# Sheet1.net
KiCad netlist of a schematic drawn in Altium Designer
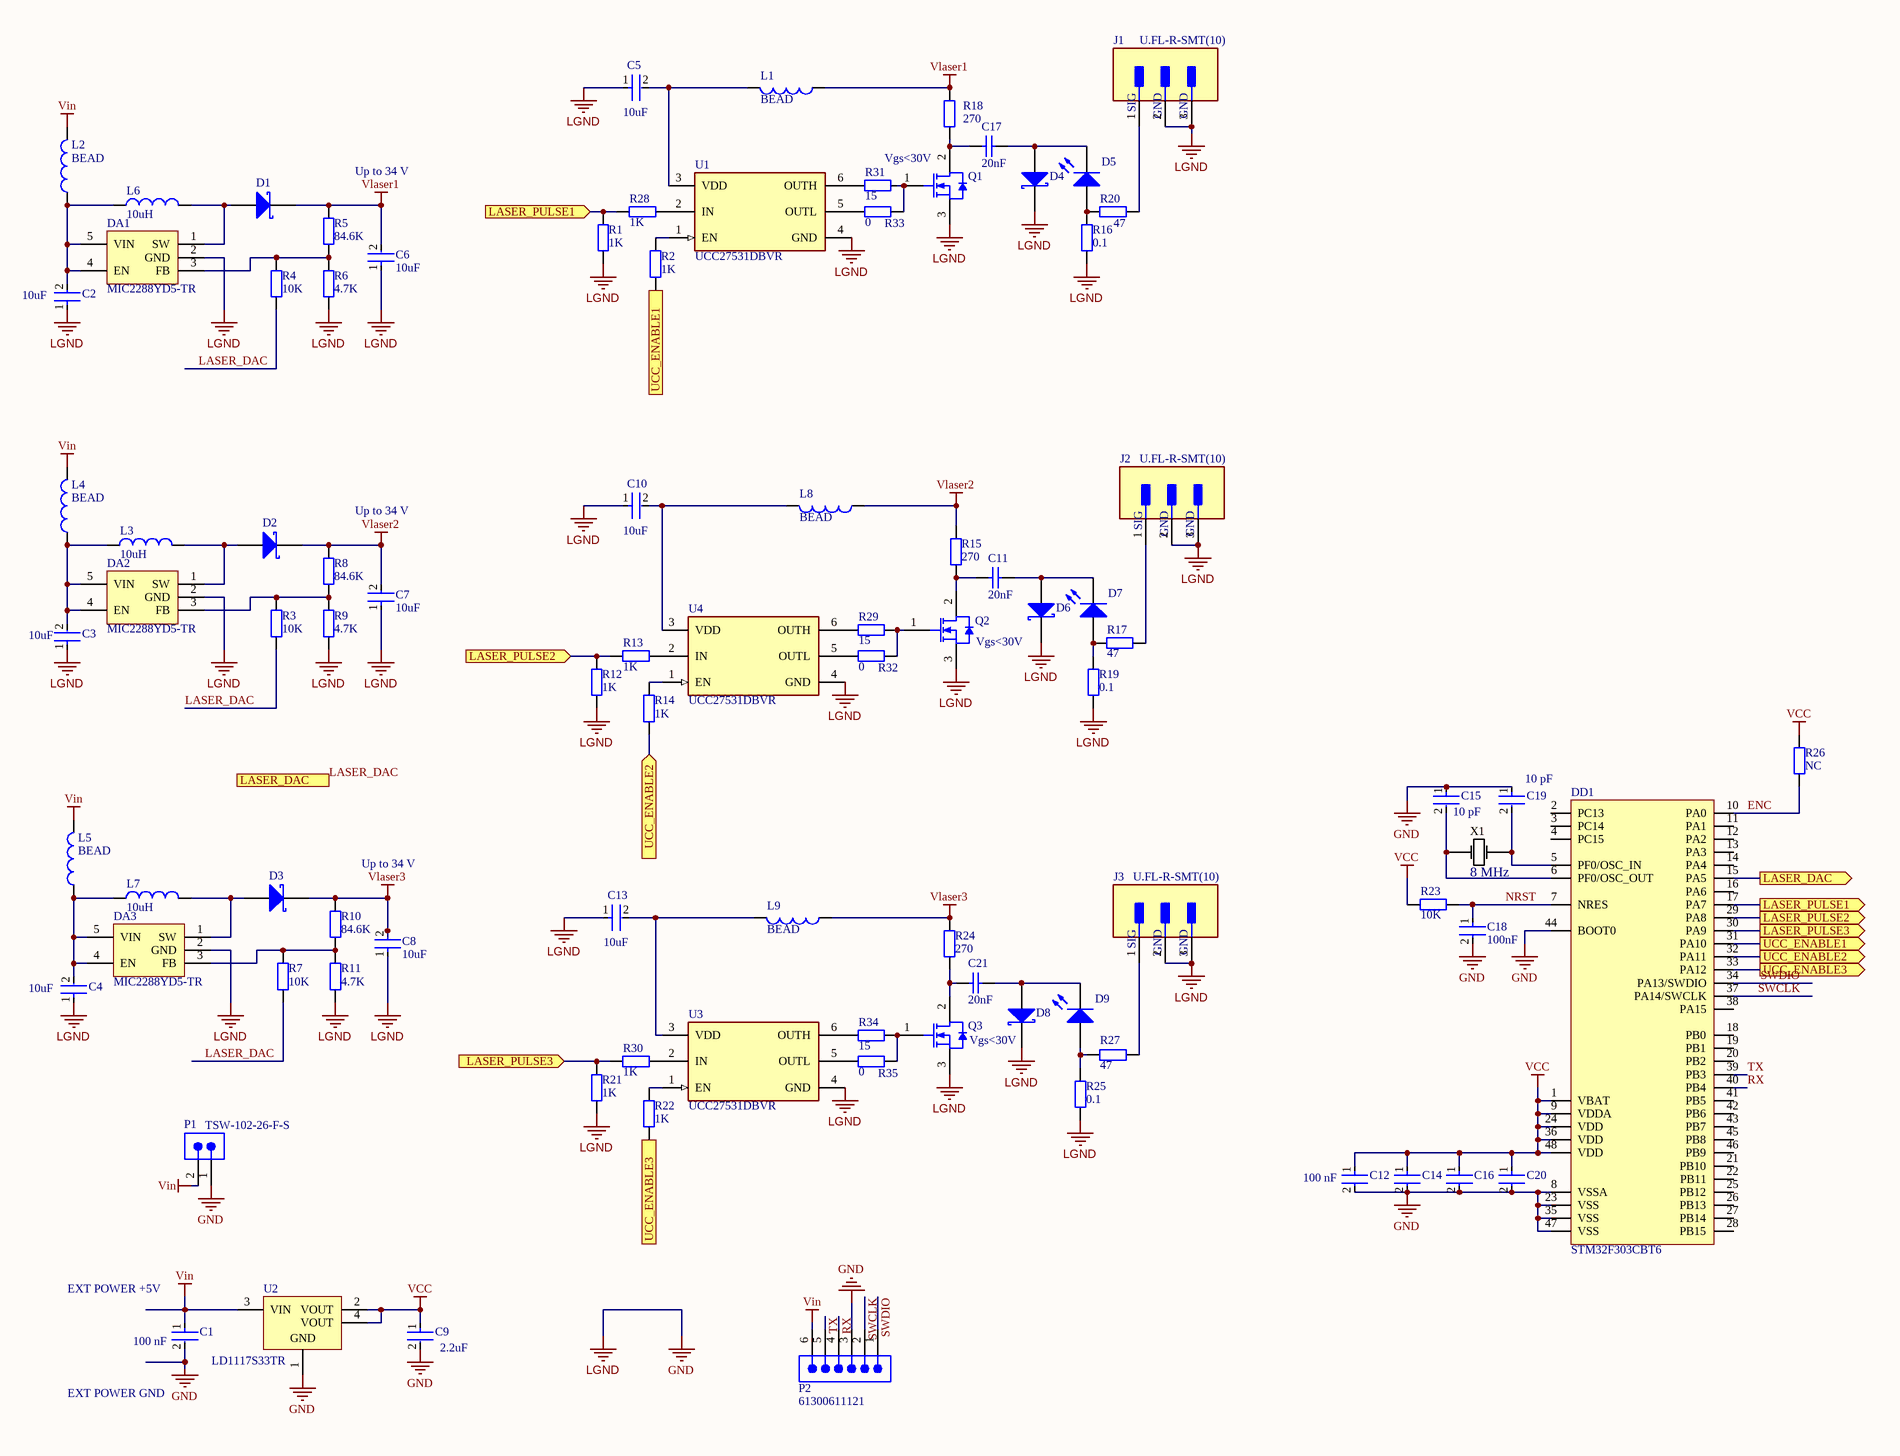
[diagram p0: Sheet1.SchDoc, right]

(export (version "E")
  (design (tool "Eeschema 10.0.6"))
  (components
    (comp (ref "C1")
      (value "100 nF")
      (footprint "FP-CC0603-DA-MFG")
      (description "CAP CER 0.1UF 16V X7R 0603")
      (fields
        (field (name "OCTOPART") "https://octopart.com/cc0603krx7r7bb104-yageo-192941")
        (field (name "TOLERANCE") "0.1")
      )
      (libsource (lib "Altium Content Vault") (part "11868f565c42a9108669ba33697ecf6"))
    )
    (comp (ref "C2")
      (value "10uF")
      (footprint "FP-CL31B106KBHNNNE-MFG")
      (description "CAP CER 10UF 50V X7R 1206")
      (fields (field (name "MANUFACTURER") "Samsung") (field (name "TOLERANCE") "10%"))
      (libsource (lib "Altium Content Vault") (part "b4654b650e69147ec39a6b967a45e02"))
    )
    (comp (ref "C3")
      (value "10uF")
      (footprint "FP-CL31B106KBHNNNE-MFG")
      (description "CAP CER 10UF 50V X7R 1206")
      (fields (field (name "MANUFACTURER") "Samsung") (field (name "TOLERANCE") "10%"))
      (libsource (lib "Altium Content Vault") (part "b4654b650e69147ec39a6b967a45e02"))
    )
    (comp (ref "C4")
      (value "10uF")
      (footprint "FP-CL31B106KBHNNNE-MFG")
      (description "CAP CER 10UF 50V X7R 1206")
      (fields (field (name "MANUFACTURER") "Samsung") (field (name "TOLERANCE") "10%"))
      (libsource (lib "Altium Content Vault") (part "b4654b650e69147ec39a6b967a45e02"))
    )
    (comp (ref "C5")
      (value "10uF")
      (footprint "FP-CL31B106KBHNNNE-MFG")
      (description "CAP CER 10UF 50V X7R 1206")
      (fields (field (name "MANUFACTURER") "Samsung") (field (name "TOLERANCE") "10%"))
      (libsource (lib "Altium Content Vault") (part "b4654b650e69147ec39a6b967a45e02"))
    )
    (comp (ref "C6")
      (value "10uF")
      (footprint "FP-CL31B106KBHNNNE-MFG")
      (description "CAP CER 10UF 50V X7R 1206")
      (fields (field (name "MANUFACTURER") "Samsung") (field (name "TOLERANCE") "10%"))
      (libsource (lib "Altium Content Vault") (part "b4654b650e69147ec39a6b967a45e02"))
    )
    (comp (ref "C7")
      (value "10uF")
      (footprint "FP-CL31B106KBHNNNE-MFG")
      (description "CAP CER 10UF 50V X7R 1206")
      (fields (field (name "MANUFACTURER") "Samsung") (field (name "TOLERANCE") "10%"))
      (libsource (lib "Altium Content Vault") (part "b4654b650e69147ec39a6b967a45e02"))
    )
    (comp (ref "C8")
      (value "10uF")
      (footprint "FP-CL31B106KBHNNNE-MFG")
      (description "CAP CER 10UF 50V X7R 1206")
      (fields (field (name "MANUFACTURER") "Samsung") (field (name "TOLERANCE") "10%"))
      (libsource (lib "Altium Content Vault") (part "b4654b650e69147ec39a6b967a45e02"))
    )
    (comp (ref "C9")
      (value "~")
      (footprint "FP-CL10-IPC_A")
      (description "Cap Ceramic 2.2uF 10V X7R ±10% Pad SMD 0603 +125°C T/R")
      (fields (field (name "CAPACITANCE") "2.2uF") (field (name "TOLERANCE") "10%"))
      (libsource (lib "Altium Content Vault") (part "b4654b650e69147ec39a6b967a45e02"))
    )
    (comp (ref "C10")
      (value "10uF")
      (footprint "FP-CL31B106KBHNNNE-MFG")
      (description "CAP CER 10UF 50V X7R 1206")
      (fields (field (name "MANUFACTURER") "Samsung") (field (name "TOLERANCE") "10%"))
      (libsource (lib "Altium Content Vault") (part "b4654b650e69147ec39a6b967a45e02"))
    )
    (comp (ref "C11")
      (value "20nF")
      (footprint "RESC2013X60X35NL10T20")
      (description "Chip capacitor")
      (fields (field (name "VOLTAGE") "50V"))
      (libsource (lib "MyLibSch") (part "CC0805"))
    )
    (comp (ref "C12")
      (value "CC0805KRX7R9BB104")
      (footprint "FP-CC0805-0_85-MFG")
      (description "CAP CER 0.1UF 50V X7R 0805")
      (fields
        (field (name "TOLERANCE") "0.1")
        (field (name "CAPACITANCE") "100 nF")
        (field (name "MANUFACTURER") "Yageo")
      )
      (libsource (lib "Altium Content Vault") (part "11868f565c42a9108669ba33697ecf6"))
    )
    (comp (ref "C13")
      (value "10uF")
      (footprint "FP-CL31B106KBHNNNE-MFG")
      (description "CAP CER 10UF 50V X7R 1206")
      (fields (field (name "MANUFACTURER") "Samsung") (field (name "TOLERANCE") "10%"))
      (libsource (lib "Altium Content Vault") (part "b4654b650e69147ec39a6b967a45e02"))
    )
    (comp (ref "C14")
      (value "CC0805KRX7R9BB104")
      (footprint "FP-CC0805-0_85-MFG")
      (description "CAP CER 0.1UF 50V X7R 0805")
      (fields (field (name "TOLERANCE") "0.1") (field (name "MANUFACTURER") "Yageo"))
      (libsource (lib "Altium Content Vault") (part "11868f565c42a9108669ba33697ecf6"))
    )
    (comp (ref "C15")
      (value "10 pF")
      (footprint "FP-C0805C-DN-MFG")
      (description "C0805 10 pF X7R 30ppm/°C 5.00% 50 V")
      (fields
        (field (name "OCTOPART") "https://octopart.com/c0805c100j5ractu-kemet-81794931")
        (field (name "MANUFACTURER PART NUMBER") "C0805C100J5RACTU")
      )
      (libsource (lib "Altium Content Vault") (part "b4654b650e69147ec39a6b967a45e02"))
    )
    (comp (ref "C16")
      (value "CC0805KRX7R9BB104")
      (footprint "FP-CC0805-0_85-MFG")
      (description "CAP CER 0.1UF 50V X7R 0805")
      (fields (field (name "TOLERANCE") "0.1") (field (name "MANUFACTURER") "Yageo"))
      (libsource (lib "Altium Content Vault") (part "11868f565c42a9108669ba33697ecf6"))
    )
    (comp (ref "C17")
      (value "20nF")
      (footprint "RESC2013X60X35ML10T20")
      (description "Chip capacitor")
      (fields (field (name "VOLTAGE") "50V"))
      (libsource (lib "MyLibSch") (part "CC0805"))
    )
    (comp (ref "C18")
      (value "100nF")
      (footprint "FP-CC0805-0_85-MFG")
      (description "CAP CER 0.1UF 50V X7R 0805")
      (fields (field (name "TOLERANCE") "0.1") (field (name "MANUFACTURER PART NUMBER") "CC0805KRX7R9BB104"))
      (libsource (lib "Altium Content Vault") (part "11868f565c42a9108669ba33697ecf6"))
    )
    (comp (ref "C19")
      (value "10 pF")
      (footprint "FP-C0805C-DN-MFG")
      (description "C0805 10 pF X7R 30ppm/°C 5.00% 50 V")
      (fields
        (field (name "OCTOPART") "https://octopart.com/c0805c100j5ractu-kemet-81794931")
        (field (name "MANUFACTURER PART NUMBER") "C0805C100J5RACTU")
      )
      (libsource (lib "Altium Content Vault") (part "b4654b650e69147ec39a6b967a45e02"))
    )
    (comp (ref "C20")
      (value "CC0805KRX7R9BB104")
      (footprint "FP-CC0805-0_85-MFG")
      (description "CAP CER 0.1UF 50V X7R 0805")
      (fields (field (name "TOLERANCE") "0.1") (field (name "MANUFACTURER") "Yageo"))
      (libsource (lib "Altium Content Vault") (part "11868f565c42a9108669ba33697ecf6"))
    )
    (comp (ref "C21")
      (value "20nF")
      (footprint "RESC2013X60X35NL10T20")
      (description "Chip capacitor")
      (fields (field (name "VOLTAGE") "50V"))
      (libsource (lib "MyLibSch") (part "CC0805"))
    )
    (comp (ref "D1")
      (value "Schottky Diode")
      (footprint "FP-PG-SC79-2-MFG")
      (libsource (lib "Simulation Generic Components") (part "Schottky Diode"))
    )
    (comp (ref "D2")
      (value "Schottky Diode")
      (footprint "FP-PG-SC79-2-MFG")
      (libsource (lib "Simulation Generic Components") (part "Schottky Diode"))
    )
    (comp (ref "D3")
      (value "Schottky Diode")
      (footprint "FP-PG-SC79-2-MFG")
      (libsource (lib "Simulation Generic Components") (part "Schottky Diode"))
    )
    (comp (ref "D4")
      (value "Schottky Diode")
      (footprint "FP-PG-SC79-2-MFG")
      (libsource (lib "Simulation Generic Components") (part "Schottky Diode"))
    )
    (comp (ref "D5")
      (value "Light-Emitting Diode")
      (footprint "FP-DPGEW1S09H-MFG")
      (libsource (lib "Simulation Generic Components") (part "LED"))
    )
    (comp (ref "D6")
      (value "Schottky Diode")
      (footprint "FP-PG-SC79-2-MFG")
      (libsource (lib "Simulation Generic Components") (part "Schottky Diode"))
    )
    (comp (ref "D7")
      (value "Light-Emitting Diode")
      (footprint "FP-DPGEW1S09H-MFG")
      (libsource (lib "Simulation Generic Components") (part "LED"))
    )
    (comp (ref "D8")
      (value "Schottky Diode")
      (footprint "FP-PG-SC79-2-MFG")
      (libsource (lib "Simulation Generic Components") (part "Schottky Diode"))
    )
    (comp (ref "D9")
      (value "Light-Emitting Diode")
      (footprint "FP-DPGEW1S09H-MFG")
      (libsource (lib "Simulation Generic Components") (part "LED"))
    )
    (comp (ref "DA1")
      (value "MIC2288YD5-TR")
      (footprint "TSOT-23-5:FP-TSOT-5LD-PL-1-IPC_A")
      (description "Step Up")
      (libsource (lib "lcd_lib") (part "MIC2288"))
    )
    (comp (ref "DA2")
      (value "MIC2288YD5-TR")
      (footprint "FP-TSOT-5LD-PL-1-IPC_A")
      (description "Step Up")
      (libsource (lib "lcd_lib") (part "MIC2288"))
    )
    (comp (ref "DA3")
      (value "MIC2288YD5-TR")
      (footprint "FP-TSOT-5LD-PL-1-IPC_A")
      (description "Step Up")
      (libsource (lib "lcd_lib") (part "MIC2288"))
    )
    (comp (ref "DD1")
      (value "STM32F303CBT6")
      (footprint "STM-LQFP48_L")
      (description "Microcontroller")
      (libsource (lib "lcd_lib") (part "STM32F3_LQFP48"))
    )
    (comp (ref "J1")
      (value "U.FL-R-SMT(10)")
      (footprint "FP-U_FL-R-SMT_10-MFG")
      (description "CONN U.FL RCPT STR 50 OHM SMD")
      (libsource (lib "Altium Content Vault") (part "eef6fde44c591823e8076210edfe12f"))
    )
    (comp (ref "J2")
      (value "U.FL-R-SMT(10)")
      (footprint "FP-U_FL-R-SMT_10-MFG")
      (description "CONN U.FL RCPT STR 50 OHM SMD")
      (libsource (lib "Altium Content Vault") (part "eef6fde44c591823e8076210edfe12f"))
    )
    (comp (ref "J3")
      (value "U.FL-R-SMT(10)")
      (footprint "FP-U_FL-R-SMT_10-MFG")
      (description "CONN U.FL RCPT STR 50 OHM SMD")
      (libsource (lib "Altium Content Vault") (part "eef6fde44c591823e8076210edfe12f"))
    )
    (comp (ref "L1")
      (value "BEAD")
      (footprint "FP-BLM18-0_15-t0_8-IPC_A")
      (description "Ferrit Bead")
      (libsource (lib "MyLibSch") (part "BEAD"))
    )
    (comp (ref "L2")
      (value "BEAD")
      (footprint "FP-BLM18-0_15-t0_8-IPC_A")
      (description "Ferrit Bead")
      (libsource (lib "MyLibSch") (part "BEAD"))
    )
    (comp (ref "L3")
      (value "10uH")
      (footprint "RESC2013X60X35LL10T20")
      (description "Inductor")
      (libsource (lib "Simulation Generic Components") (part "Inductor"))
    )
    (comp (ref "L4")
      (value "BEAD")
      (footprint "FP-BLM18-0_15-t0_8-IPC_A")
      (description "Ferrit Bead")
      (libsource (lib "MyLibSch") (part "BEAD"))
    )
    (comp (ref "L5")
      (value "BEAD")
      (footprint "FP-BLM18-0_15-t0_8-IPC_A")
      (description "Ferrit Bead")
      (libsource (lib "MyLibSch") (part "BEAD"))
    )
    (comp (ref "L6")
      (value "10uH")
      (footprint "RESC2013X60X35LL10T20")
      (description "Inductor")
      (libsource (lib "Simulation Generic Components") (part "Inductor"))
    )
    (comp (ref "L7")
      (value "10uH")
      (footprint "RESC2013X60X35LL10T20")
      (description "Inductor")
      (libsource (lib "Simulation Generic Components") (part "Inductor"))
    )
    (comp (ref "L8")
      (value "BEAD")
      (footprint "FP-BLM18-0_15-t0_8-IPC_A")
      (description "Ferrit Bead")
      (libsource (lib "MyLibSch") (part "BEAD"))
    )
    (comp (ref "L9")
      (value "BEAD")
      (footprint "FP-BLM18-0_15-t0_8-IPC_A")
      (description "Ferrit Bead")
      (libsource (lib "MyLibSch") (part "BEAD"))
    )
    (comp (ref "P1")
      (value "TSW-102-26-F-S")
      (footprint "SMTC-TSW-102-26-XX-S")
      (description "0.025\" SQ Post Header, Through-hole, Vertical, -55 to 125 degC, 2.54 mm Pitch, 2-Pin, Male, RoHS")
      (fields (field (name "MANUFACTURER") "Samtec"))
      (libsource (lib "Altium Content Vault") (part "SMTC-TSW-102-X-X-S-X"))
    )
    (comp (ref "P2")
      (value "61300611121")
      (footprint "61300611121")
      (libsource (lib "Altium Content Vault") (part "Header_Male_1R_06P"))
    )
    (comp (ref "Q1")
      (value "~")
      (footprint "INF-PG-TO252-3-313_N")
      (fields (field (name "MANUFACTURER") "Infineon") (field (name "PARTNUMBER") "IPD60R520C6"))
      (libsource (lib "Components - 15.04.25 - 21.51") (part "CMP-1164-00353-1"))
    )
    (comp (ref "Q2")
      (value "~")
      (footprint "INF-PG-TO252-3-313_N")
      (fields (field (name "MANUFACTURER") "Infineon") (field (name "PARTNUMBER") "IPD60R520C6"))
      (libsource (lib "Components - 15.04.25 - 21.51") (part "CMP-1164-00353-1"))
    )
    (comp (ref "Q3")
      (value "~")
      (footprint "INF-PG-TO252-3-313_N")
      (fields (field (name "MANUFACTURER") "Infineon") (field (name "PARTNUMBER") "IPD60R520C6"))
      (libsource (lib "Components - 15.04.25 - 21.51") (part "CMP-1164-00353-1"))
    )
    (comp (ref "R1")
      (value "1K")
      (footprint "RESC2013X60X35ML10T20")
      (description "Chip resistor")
      (fields (field (name "TOLERANCE") "5%"))
      (libsource (lib "") (part "RC0805_1"))
    )
    (comp (ref "R2")
      (value "1K")
      (footprint "RESC2013X60X35ML10T20")
      (description "Chip resistor")
      (fields (field (name "TOLERANCE") "5%"))
      (libsource (lib "") (part "RC0805_1"))
    )
    (comp (ref "R3")
      (value "10K")
      (footprint "RESC2013X60X35ML10T20")
      (description "Chip resistor")
      (fields (field (name "TOLERANCE") "5%"))
      (libsource (lib "") (part "RC0805_1"))
    )
    (comp (ref "R4")
      (value "10K")
      (footprint "RESC2013X60X35ML10T20")
      (description "Chip resistor")
      (fields (field (name "TOLERANCE") "5%"))
      (libsource (lib "") (part "RC0805_1"))
    )
    (comp (ref "R5")
      (value "84.6K")
      (footprint "RESC2013X60X35ML10T20")
      (description "Chip resistor")
      (fields (field (name "TOLERANCE") "5%"))
      (libsource (lib "") (part "RC0805_1"))
    )
    (comp (ref "R6")
      (value "4.7K")
      (footprint "RESC2013X60X35ML10T20")
      (description "Chip resistor")
      (fields (field (name "TOLERANCE") "5%"))
      (libsource (lib "") (part "RC0805_1"))
    )
    (comp (ref "R7")
      (value "10K")
      (footprint "RESC2013X60X35ML10T20")
      (description "Chip resistor")
      (fields (field (name "TOLERANCE") "5%"))
      (libsource (lib "") (part "RC0805_1"))
    )
    (comp (ref "R8")
      (value "84.6K")
      (footprint "RESC2013X60X35ML10T20")
      (description "Chip resistor")
      (fields (field (name "TOLERANCE") "5%"))
      (libsource (lib "") (part "RC0805_1"))
    )
    (comp (ref "R9")
      (value "4.7K")
      (footprint "RESC2013X60X35ML10T20")
      (description "Chip resistor")
      (fields (field (name "TOLERANCE") "5%"))
      (libsource (lib "") (part "RC0805_1"))
    )
    (comp (ref "R10")
      (value "84.6K")
      (footprint "RESC2013X60X35ML10T20")
      (description "Chip resistor")
      (fields (field (name "TOLERANCE") "5%"))
      (libsource (lib "") (part "RC0805_1"))
    )
    (comp (ref "R11")
      (value "4.7K")
      (footprint "RESC2013X60X35ML10T20")
      (description "Chip resistor")
      (fields (field (name "TOLERANCE") "5%"))
      (libsource (lib "") (part "RC0805_1"))
    )
    (comp (ref "R12")
      (value "1K")
      (footprint "RESC2013X60X35ML10T20")
      (description "Chip resistor")
      (fields (field (name "TOLERANCE") "5%"))
      (libsource (lib "") (part "RC0805_1"))
    )
    (comp (ref "R13")
      (value "1K")
      (footprint "RESC2013X60X35ML10T20")
      (description "Chip resistor")
      (fields (field (name "TOLERANCE") "5%"))
      (libsource (lib "") (part "RC0805_2"))
    )
    (comp (ref "R14")
      (value "1K")
      (footprint "RESC2013X60X35ML10T20")
      (description "Chip resistor")
      (fields (field (name "TOLERANCE") "5%"))
      (libsource (lib "") (part "RC0805_1"))
    )
    (comp (ref "R15")
      (value "270")
      (footprint "FP-CL31B106KBHNNNE-IPC_A")
      (description "Chip resistor")
      (fields (field (name "TOLERANCE") "5%"))
      (libsource (lib "") (part "RC0805_1"))
    )
    (comp (ref "R16")
      (value "0.1")
      (footprint "FP-LLL215-0_1-IPC_B")
      (description "Chip resistor")
      (fields (field (name "TOLERANCE") "5%"))
      (libsource (lib "") (part "RC0805_1"))
    )
    (comp (ref "R17")
      (value "47")
      (footprint "RESC2013X60X35ML10T20")
      (description "Chip resistor")
      (fields (field (name "TOLERANCE") "5%"))
      (libsource (lib "") (part "RC0805_2"))
    )
    (comp (ref "R18")
      (value "270")
      (footprint "FP-CL31B106KBHNNNE-IPC_A")
      (description "Chip resistor")
      (fields (field (name "TOLERANCE") "5%"))
      (libsource (lib "") (part "RC0805_1"))
    )
    (comp (ref "R19")
      (value "0.1")
      (footprint "FP-LLL215-0_1-IPC_B")
      (description "Chip resistor")
      (fields (field (name "TOLERANCE") "5%"))
      (libsource (lib "") (part "RC0805_1"))
    )
    (comp (ref "R20")
      (value "47")
      (footprint "RESC2013X60X35ML10T20")
      (description "Chip resistor")
      (fields (field (name "TOLERANCE") "5%"))
      (libsource (lib "MyLibSch") (part "RC0805"))
    )
    (comp (ref "R21")
      (value "1K")
      (footprint "RESC2013X60X35ML10T20")
      (description "Chip resistor")
      (fields (field (name "TOLERANCE") "5%"))
      (libsource (lib "") (part "RC0805_1"))
    )
    (comp (ref "R22")
      (value "1K")
      (footprint "RESC2013X60X35ML10T20")
      (description "Chip resistor")
      (fields (field (name "TOLERANCE") "5%"))
      (libsource (lib "") (part "RC0805_1"))
    )
    (comp (ref "R23")
      (value "10K")
      (footprint "RESC2013X60X35ML10T20")
      (description "Chip resistor")
      (fields (field (name "TOLERANCE") "5%"))
      (libsource (lib "MyLibSch") (part "RC0805"))
    )
    (comp (ref "R24")
      (value "270")
      (footprint "FP-CL31B106KBHNNNE-IPC_A")
      (description "Chip resistor")
      (fields (field (name "TOLERANCE") "5%"))
      (libsource (lib "") (part "RC0805_1"))
    )
    (comp (ref "R25")
      (value "0.1")
      (footprint "FP-LLL215-0_1-IPC_B")
      (description "Chip resistor")
      (fields (field (name "TOLERANCE") "5%"))
      (libsource (lib "") (part "RC0805_1"))
    )
    (comp (ref "R26")
      (value "NC")
      (footprint "RESC2013X60X35ML10T20")
      (description "Chip resistor")
      (fields (field (name "TOLERANCE") "5%"))
      (libsource (lib "") (part "RC0805_3"))
    )
    (comp (ref "R27")
      (value "47")
      (footprint "RESC2013X60X35ML10T20")
      (description "Chip resistor")
      (fields (field (name "TOLERANCE") "5%"))
      (libsource (lib "MyLibSch") (part "RC0805"))
    )
    (comp (ref "R28")
      (value "1K")
      (footprint "RESC2013X60X35ML10T20")
      (description "Chip resistor")
      (fields (field (name "TOLERANCE") "5%"))
      (libsource (lib "") (part "RC0805_2"))
    )
    (comp (ref "R29")
      (value "15")
      (footprint "RESC2013X60X35ML10T20")
      (description "Chip resistor")
      (fields (field (name "TOLERANCE") "5%"))
      (libsource (lib "") (part "RC0805_2"))
    )
    (comp (ref "R30")
      (value "1K")
      (footprint "RESC2013X60X35ML10T20")
      (description "Chip resistor")
      (fields (field (name "TOLERANCE") "5%"))
      (libsource (lib "") (part "RC0805_2"))
    )
    (comp (ref "R31")
      (value "15")
      (footprint "RESC2013X60X35ML10T20")
      (description "Chip resistor")
      (fields (field (name "TOLERANCE") "5%"))
      (libsource (lib "") (part "RC0805_2"))
    )
    (comp (ref "R32")
      (value "0")
      (footprint "RESC2013X60X35ML10T20")
      (description "Chip resistor")
      (fields (field (name "TOLERANCE") "5%"))
      (libsource (lib "") (part "RC0805_2"))
    )
    (comp (ref "R33")
      (value "0")
      (footprint "RESC2013X60X35ML10T20")
      (description "Chip resistor")
      (fields (field (name "TOLERANCE") "5%"))
      (libsource (lib "") (part "RC0805_2"))
    )
    (comp (ref "R34")
      (value "15")
      (footprint "RESC2013X60X35ML10T20")
      (description "Chip resistor")
      (fields (field (name "TOLERANCE") "5%"))
      (libsource (lib "") (part "RC0805_2"))
    )
    (comp (ref "R35")
      (value "0")
      (footprint "RESC2013X60X35ML10T20")
      (description "Chip resistor")
      (fields (field (name "TOLERANCE") "5%"))
      (libsource (lib "") (part "RC0805_2"))
    )
    (comp (ref "U1")
      (value "UCC27531DBVR")
      (footprint "FP-DBV0006A-IPC_B")
      (description "IC GATE DRVR LOW-SIDE SOT23-6")
      (libsource (lib "Altium Content Vault") (part "16a91a241c20d76ff8c7580b319091c"))
    )
    (comp (ref "U2")
      (value "LD1117S33TR")
      (footprint "SOT-223_L")
      (description "Fixed Low Drop Positive Voltage Regulator, 3.3V, 4-Pin SOT-223, Tape and Reel")
      (libsource (lib "Altium Content Vault") (part "PM-REG-LD1117-SOT4"))
    )
    (comp (ref "U3")
      (value "UCC27531DBVR")
      (footprint "FP-DBV0006A-IPC_B")
      (description "IC GATE DRVR LOW-SIDE SOT23-6")
      (libsource (lib "Altium Content Vault") (part "16a91a241c20d76ff8c7580b319091c"))
    )
    (comp (ref "U4")
      (value "UCC27531DBVR")
      (footprint "FP-DBV0006A-IPC_B")
      (description "IC GATE DRVR LOW-SIDE SOT23-6")
      (libsource (lib "Altium Content Vault") (part "16a91a241c20d76ff8c7580b319091c"))
    )
    (comp (ref "X1")
      (value "8 MHz")
      (footprint "FP-ASFL1-MFG")
      (description "Quartz_SX-6 (SMD06035C4)")
      (fields (field (name "Comment") "Quartz"))
      (libsource (lib "lcd_lib") (part "Quartz_SX-6"))
    )
  )
  (nets
    (net (code "1") (name "/ENC") (class "Default")
      (node (ref "DD1") (pin "10") (pinfunction "PA0_10") (pintype "passive"))
      (node (ref "R26") (pin "2") (pinfunction "2_2") (pintype "passive"))
    )
    (net (code "2") (name "/LASER_DAC") (class "Default")
      (node (ref "DD1") (pin "15") (pinfunction "PA5_15") (pintype "passive"))
      (node (ref "R3") (pin "1") (pinfunction "1_1") (pintype "passive"))
      (node (ref "R4") (pin "1") (pinfunction "1_1") (pintype "passive"))
      (node (ref "R7") (pin "1") (pinfunction "1_1") (pintype "passive"))
    )
    (net (code "3") (name "/LASER_PULSE1") (class "Default")
      (node (ref "DD1") (pin "17") (pinfunction "PA7_17") (pintype "passive"))
      (node (ref "R1") (pin "2") (pinfunction "2_2") (pintype "passive"))
      (node (ref "R28") (pin "2") (pinfunction "2_2") (pintype "passive"))
    )
    (net (code "4") (name "/LASER_PULSE2") (class "Default")
      (node (ref "DD1") (pin "29") (pinfunction "PA8_29") (pintype "passive"))
      (node (ref "R12") (pin "2") (pinfunction "2_2") (pintype "passive"))
      (node (ref "R13") (pin "2") (pinfunction "2_2") (pintype "passive"))
    )
    (net (code "5") (name "/LASER_PULSE3") (class "Default")
      (node (ref "DD1") (pin "30") (pinfunction "PA9_30") (pintype "passive"))
      (node (ref "R21") (pin "2") (pinfunction "2_2") (pintype "passive"))
      (node (ref "R30") (pin "2") (pinfunction "2_2") (pintype "passive"))
    )
    (net (code "6") (name "/NRST") (class "Default")
      (node (ref "C18") (pin "1") (pinfunction "1_1") (pintype "passive"))
      (node (ref "DD1") (pin "7") (pinfunction "NRES_7") (pintype "passive"))
      (node (ref "R23") (pin "2") (pinfunction "2_2") (pintype "passive"))
    )
    (net (code "7") (name "/RX") (class "Default")
      (node (ref "DD1") (pin "40") (pinfunction "PB4_40") (pintype "passive"))
      (node (ref "P2") (pin "4") (pinfunction "4_4") (pintype "passive"))
    )
    (net (code "8") (name "/SWCLK") (class "Default")
      (node (ref "DD1") (pin "37") (pinfunction "PA14/SWCLK_37") (pintype "passive"))
      (node (ref "P2") (pin "2") (pinfunction "2_2") (pintype "passive"))
    )
    (net (code "9") (name "/SWDIO") (class "Default")
      (node (ref "DD1") (pin "34") (pinfunction "PA13/SWDIO_34") (pintype "passive"))
      (node (ref "P2") (pin "1") (pinfunction "1_1") (pintype "passive"))
    )
    (net (code "10") (name "/TX") (class "Default")
      (node (ref "DD1") (pin "39") (pinfunction "PB3_39") (pintype "passive"))
      (node (ref "P2") (pin "5") (pinfunction "5_5") (pintype "passive"))
    )
    (net (code "11") (name "/UCC_ENABLE1") (class "Default")
      (node (ref "DD1") (pin "31") (pinfunction "PA10_31") (pintype "passive"))
      (node (ref "R2") (pin "1") (pinfunction "1_1") (pintype "passive"))
    )
    (net (code "12") (name "/UCC_ENABLE2") (class "Default")
      (node (ref "DD1") (pin "32") (pinfunction "PA11_32") (pintype "passive"))
      (node (ref "R14") (pin "1") (pinfunction "1_1") (pintype "passive"))
    )
    (net (code "13") (name "/UCC_ENABLE3") (class "Default")
      (node (ref "DD1") (pin "33") (pinfunction "PA12_33") (pintype "passive"))
      (node (ref "R22") (pin "1") (pinfunction "1_1") (pintype "passive"))
    )
    (net (code "14") (name "GND") (class "Default")
      (node (ref "C1") (pin "2") (pinfunction "2_2") (pintype "passive"))
      (node (ref "C10") (pin "1") (pinfunction "1_1") (pintype "passive"))
      (node (ref "C12") (pin "2") (pinfunction "2_2") (pintype "passive"))
      (node (ref "C13") (pin "1") (pinfunction "1_1") (pintype "passive"))
      (node (ref "C14") (pin "2") (pinfunction "2_2") (pintype "passive"))
      (node (ref "C15") (pin "1") (pinfunction "1_1") (pintype "passive"))
      (node (ref "C16") (pin "2") (pinfunction "2_2") (pintype "passive"))
      (node (ref "C18") (pin "2") (pinfunction "2_2") (pintype "passive"))
      (node (ref "C19") (pin "1") (pinfunction "1_1") (pintype "passive"))
      (node (ref "C2") (pin "1") (pinfunction "1_1") (pintype "passive"))
      (node (ref "C20") (pin "2") (pinfunction "2_2") (pintype "passive"))
      (node (ref "C3") (pin "1") (pinfunction "1_1") (pintype "passive"))
      (node (ref "C4") (pin "1") (pinfunction "1_1") (pintype "passive"))
      (node (ref "C5") (pin "1") (pinfunction "1_1") (pintype "passive"))
      (node (ref "C6") (pin "1") (pinfunction "1_1") (pintype "passive"))
      (node (ref "C7") (pin "1") (pinfunction "1_1") (pintype "passive"))
      (node (ref "C8") (pin "1") (pinfunction "1_1") (pintype "passive"))
      (node (ref "C9") (pin "2") (pinfunction "2_2") (pintype "passive"))
      (node (ref "D4") (pin "2") (pinfunction "K_2") (pintype "passive"))
      (node (ref "D6") (pin "2") (pinfunction "K_2") (pintype "passive"))
      (node (ref "D8") (pin "2") (pinfunction "K_2") (pintype "passive"))
      (node (ref "DA1") (pin "2") (pinfunction "GND_2") (pintype "power_in"))
      (node (ref "DA2") (pin "2") (pinfunction "GND_2") (pintype "power_in"))
      (node (ref "DA3") (pin "2") (pinfunction "GND_2") (pintype "power_in"))
      (node (ref "DD1") (pin "23") (pinfunction "VSS_23") (pintype "passive"))
      (node (ref "DD1") (pin "35") (pinfunction "VSS_35") (pintype "passive"))
      (node (ref "DD1") (pin "44") (pinfunction "BOOT0_44") (pintype "passive"))
      (node (ref "DD1") (pin "47") (pinfunction "VSS_47") (pintype "passive"))
      (node (ref "DD1") (pin "8") (pinfunction "VSSA_8") (pintype "passive"))
      (node (ref "J1") (pin "2") (pinfunction "GND_2") (pintype "power_in"))
      (node (ref "J1") (pin "3") (pinfunction "GND_3") (pintype "power_in"))
      (node (ref "J2") (pin "2") (pinfunction "GND_2") (pintype "power_in"))
      (node (ref "J2") (pin "3") (pinfunction "GND_3") (pintype "power_in"))
      (node (ref "J3") (pin "2") (pinfunction "GND_2") (pintype "power_in"))
      (node (ref "J3") (pin "3") (pinfunction "GND_3") (pintype "power_in"))
      (node (ref "P1") (pin "1") (pinfunction "1_1") (pintype "passive"))
      (node (ref "P2") (pin "3") (pinfunction "3_3") (pintype "passive"))
      (node (ref "Q1") (pin "3") (pinfunction "SOURCE_3") (pintype "passive"))
      (node (ref "Q2") (pin "3") (pinfunction "SOURCE_3") (pintype "passive"))
      (node (ref "Q3") (pin "3") (pinfunction "SOURCE_3") (pintype "passive"))
      (node (ref "R1") (pin "1") (pinfunction "1_1") (pintype "passive"))
      (node (ref "R11") (pin "1") (pinfunction "1_1") (pintype "passive"))
      (node (ref "R12") (pin "1") (pinfunction "1_1") (pintype "passive"))
      (node (ref "R16") (pin "1") (pinfunction "1_1") (pintype "passive"))
      (node (ref "R19") (pin "1") (pinfunction "1_1") (pintype "passive"))
      (node (ref "R21") (pin "1") (pinfunction "1_1") (pintype "passive"))
      (node (ref "R25") (pin "1") (pinfunction "1_1") (pintype "passive"))
      (node (ref "R6") (pin "1") (pinfunction "1_1") (pintype "passive"))
      (node (ref "R9") (pin "1") (pinfunction "1_1") (pintype "passive"))
      (node (ref "U1") (pin "4") (pinfunction "GND_4") (pintype "power_in"))
      (node (ref "U2") (pin "1") (pinfunction "GND_1") (pintype "power_in"))
      (node (ref "U3") (pin "4") (pinfunction "GND_4") (pintype "power_in"))
      (node (ref "U4") (pin "4") (pinfunction "GND_4") (pintype "power_in"))
    )
    (net (code "15") (name "Net-(D1-A)") (class "Default")
      (node (ref "D1") (pin "1") (pinfunction "A_1") (pintype "passive"))
      (node (ref "DA1") (pin "1") (pinfunction "SW_1") (pintype "open_collector"))
      (node (ref "L6") (pin "2") (pinfunction "2_2") (pintype "passive"))
    )
    (net (code "16") (name "Net-(D2-A)") (class "Default")
      (node (ref "D2") (pin "1") (pinfunction "A_1") (pintype "passive"))
      (node (ref "DA2") (pin "1") (pinfunction "SW_1") (pintype "open_collector"))
      (node (ref "L3") (pin "2") (pinfunction "2_2") (pintype "passive"))
    )
    (net (code "17") (name "Net-(D3-A)") (class "Default")
      (node (ref "D3") (pin "1") (pinfunction "A_1") (pintype "passive"))
      (node (ref "DA3") (pin "1") (pinfunction "SW_1") (pintype "open_collector"))
      (node (ref "L7") (pin "2") (pinfunction "2_2") (pintype "passive"))
    )
    (net (code "18") (name "Net-(D4-A)") (class "Default")
      (node (ref "C17") (pin "1") (pinfunction "1_1") (pintype "passive"))
      (node (ref "D4") (pin "1") (pinfunction "A_1") (pintype "passive"))
      (node (ref "D5") (pin "2") (pinfunction "K_2") (pintype "passive"))
    )
    (net (code "19") (name "Net-(D5-A)") (class "Default")
      (node (ref "D5") (pin "1") (pinfunction "A_1") (pintype "passive"))
      (node (ref "R16") (pin "2") (pinfunction "2_2") (pintype "passive"))
      (node (ref "R20") (pin "1") (pinfunction "1_1") (pintype "passive"))
    )
    (net (code "20") (name "Net-(D6-A)") (class "Default")
      (node (ref "C11") (pin "1") (pinfunction "1_1") (pintype "passive"))
      (node (ref "D6") (pin "1") (pinfunction "A_1") (pintype "passive"))
      (node (ref "D7") (pin "2") (pinfunction "K_2") (pintype "passive"))
    )
    (net (code "21") (name "Net-(D7-A)") (class "Default")
      (node (ref "D7") (pin "1") (pinfunction "A_1") (pintype "passive"))
      (node (ref "R17") (pin "2") (pinfunction "2_2") (pintype "passive"))
      (node (ref "R19") (pin "2") (pinfunction "2_2") (pintype "passive"))
    )
    (net (code "22") (name "Net-(D8-A)") (class "Default")
      (node (ref "C21") (pin "1") (pinfunction "1_1") (pintype "passive"))
      (node (ref "D8") (pin "1") (pinfunction "A_1") (pintype "passive"))
      (node (ref "D9") (pin "2") (pinfunction "K_2") (pintype "passive"))
    )
    (net (code "23") (name "Net-(D9-A)") (class "Default")
      (node (ref "D9") (pin "1") (pinfunction "A_1") (pintype "passive"))
      (node (ref "R25") (pin "2") (pinfunction "2_2") (pintype "passive"))
      (node (ref "R27") (pin "1") (pinfunction "1_1") (pintype "passive"))
    )
    (net (code "24") (name "Net-(DA1-EN)") (class "Default")
      (node (ref "C2") (pin "2") (pinfunction "2_2") (pintype "passive"))
      (node (ref "DA1") (pin "4") (pinfunction "EN_4") (pintype "power_in"))
      (node (ref "DA1") (pin "5") (pinfunction "VIN_5") (pintype "passive"))
      (node (ref "L2") (pin "1") (pinfunction "1_1") (pintype "passive"))
      (node (ref "L6") (pin "1") (pinfunction "1_1") (pintype "passive"))
    )
    (net (code "25") (name "Net-(DA1-FB)") (class "Default")
      (node (ref "DA1") (pin "3") (pinfunction "FB_3") (pintype "power_in"))
      (node (ref "R4") (pin "2") (pinfunction "2_2") (pintype "passive"))
      (node (ref "R5") (pin "1") (pinfunction "1_1") (pintype "passive"))
      (node (ref "R6") (pin "2") (pinfunction "2_2") (pintype "passive"))
    )
    (net (code "26") (name "Net-(DA2-EN)") (class "Default")
      (node (ref "C3") (pin "2") (pinfunction "2_2") (pintype "passive"))
      (node (ref "DA2") (pin "4") (pinfunction "EN_4") (pintype "power_in"))
      (node (ref "DA2") (pin "5") (pinfunction "VIN_5") (pintype "passive"))
      (node (ref "L3") (pin "1") (pinfunction "1_1") (pintype "passive"))
      (node (ref "L4") (pin "1") (pinfunction "1_1") (pintype "passive"))
    )
    (net (code "27") (name "Net-(DA2-FB)") (class "Default")
      (node (ref "DA2") (pin "3") (pinfunction "FB_3") (pintype "power_in"))
      (node (ref "R3") (pin "2") (pinfunction "2_2") (pintype "passive"))
      (node (ref "R8") (pin "1") (pinfunction "1_1") (pintype "passive"))
      (node (ref "R9") (pin "2") (pinfunction "2_2") (pintype "passive"))
    )
    (net (code "28") (name "Net-(DA3-EN)") (class "Default")
      (node (ref "C4") (pin "2") (pinfunction "2_2") (pintype "passive"))
      (node (ref "DA3") (pin "4") (pinfunction "EN_4") (pintype "power_in"))
      (node (ref "DA3") (pin "5") (pinfunction "VIN_5") (pintype "passive"))
      (node (ref "L5") (pin "1") (pinfunction "1_1") (pintype "passive"))
      (node (ref "L7") (pin "1") (pinfunction "1_1") (pintype "passive"))
    )
    (net (code "29") (name "Net-(DA3-FB)") (class "Default")
      (node (ref "DA3") (pin "3") (pinfunction "FB_3") (pintype "power_in"))
      (node (ref "R10") (pin "1") (pinfunction "1_1") (pintype "passive"))
      (node (ref "R11") (pin "2") (pinfunction "2_2") (pintype "passive"))
      (node (ref "R7") (pin "2") (pinfunction "2_2") (pintype "passive"))
    )
    (net (code "30") (name "Net-(DD1-PF0{slash}OSC_IN)") (class "Default")
      (node (ref "C19") (pin "2") (pinfunction "2_2") (pintype "passive"))
      (node (ref "DD1") (pin "5") (pinfunction "PF0/OSC_IN_5") (pintype "passive"))
      (node (ref "X1") (pin "3") (pinfunction "3_3") (pintype "passive"))
    )
    (net (code "31") (name "Net-(DD1-PF0{slash}OSC_OUT)") (class "Default")
      (node (ref "C15") (pin "2") (pinfunction "2_2") (pintype "passive"))
      (node (ref "DD1") (pin "6") (pinfunction "PF0/OSC_OUT_6") (pintype "passive"))
      (node (ref "X1") (pin "1") (pinfunction "1_1") (pintype "passive"))
    )
    (net (code "32") (name "Net-(J1-SIG)") (class "Default")
      (node (ref "J1") (pin "1") (pinfunction "SIG_1") (pintype "passive"))
      (node (ref "R20") (pin "2") (pinfunction "2_2") (pintype "passive"))
    )
    (net (code "33") (name "Net-(J2-SIG)") (class "Default")
      (node (ref "J2") (pin "1") (pinfunction "SIG_1") (pintype "passive"))
      (node (ref "R17") (pin "1") (pinfunction "1_1") (pintype "passive"))
    )
    (net (code "34") (name "Net-(J3-SIG)") (class "Default")
      (node (ref "J3") (pin "1") (pinfunction "SIG_1") (pintype "passive"))
      (node (ref "R27") (pin "2") (pinfunction "2_2") (pintype "passive"))
    )
    (net (code "35") (name "Net-(Q1-DRAIN)") (class "Default")
      (node (ref "C17") (pin "2") (pinfunction "2_2") (pintype "passive"))
      (node (ref "Q1") (pin "2") (pinfunction "DRAIN_2") (pintype "passive"))
      (node (ref "R18") (pin "1") (pinfunction "1_1") (pintype "passive"))
    )
    (net (code "36") (name "Net-(Q1-GATE)") (class "Default")
      (node (ref "Q1") (pin "1") (pinfunction "GATE_1") (pintype "passive"))
      (node (ref "R31") (pin "1") (pinfunction "1_1") (pintype "passive"))
      (node (ref "R33") (pin "1") (pinfunction "1_1") (pintype "passive"))
    )
    (net (code "37") (name "Net-(Q2-DRAIN)") (class "Default")
      (node (ref "C11") (pin "2") (pinfunction "2_2") (pintype "passive"))
      (node (ref "Q2") (pin "2") (pinfunction "DRAIN_2") (pintype "passive"))
      (node (ref "R15") (pin "1") (pinfunction "1_1") (pintype "passive"))
    )
    (net (code "38") (name "Net-(Q2-GATE)") (class "Default")
      (node (ref "Q2") (pin "1") (pinfunction "GATE_1") (pintype "passive"))
      (node (ref "R29") (pin "1") (pinfunction "1_1") (pintype "passive"))
      (node (ref "R32") (pin "1") (pinfunction "1_1") (pintype "passive"))
    )
    (net (code "39") (name "Net-(Q3-DRAIN)") (class "Default")
      (node (ref "C21") (pin "2") (pinfunction "2_2") (pintype "passive"))
      (node (ref "Q3") (pin "2") (pinfunction "DRAIN_2") (pintype "passive"))
      (node (ref "R24") (pin "1") (pinfunction "1_1") (pintype "passive"))
    )
    (net (code "40") (name "Net-(Q3-GATE)") (class "Default")
      (node (ref "Q3") (pin "1") (pinfunction "GATE_1") (pintype "passive"))
      (node (ref "R34") (pin "1") (pinfunction "1_1") (pintype "passive"))
      (node (ref "R35") (pin "1") (pinfunction "1_1") (pintype "passive"))
    )
    (net (code "41") (name "Net-(U1-EN)") (class "Default")
      (node (ref "R2") (pin "2") (pinfunction "2_2") (pintype "passive"))
      (node (ref "U1") (pin "1") (pinfunction "EN_1") (pintype "input"))
    )
    (net (code "42") (name "Net-(U1-IN)") (class "Default")
      (node (ref "R28") (pin "1") (pinfunction "1_1") (pintype "passive"))
      (node (ref "U1") (pin "2") (pinfunction "IN_2") (pintype "tri_state"))
    )
    (net (code "43") (name "Net-(U1-OUTH)") (class "Default")
      (node (ref "R31") (pin "2") (pinfunction "2_2") (pintype "passive"))
      (node (ref "U1") (pin "6") (pinfunction "OUTH_6") (pintype "passive"))
    )
    (net (code "44") (name "Net-(U1-OUTL)") (class "Default")
      (node (ref "R33") (pin "2") (pinfunction "2_2") (pintype "passive"))
      (node (ref "U1") (pin "5") (pinfunction "OUTL_5") (pintype "passive"))
    )
    (net (code "45") (name "Net-(U1-VDD)") (class "Default")
      (node (ref "C5") (pin "2") (pinfunction "2_2") (pintype "passive"))
      (node (ref "L1") (pin "2") (pinfunction "2_2") (pintype "passive"))
      (node (ref "U1") (pin "3") (pinfunction "VDD_3") (pintype "power_in"))
    )
    (net (code "46") (name "Net-(U3-EN)") (class "Default")
      (node (ref "R22") (pin "2") (pinfunction "2_2") (pintype "passive"))
      (node (ref "U3") (pin "1") (pinfunction "EN_1") (pintype "input"))
    )
    (net (code "47") (name "Net-(U3-IN)") (class "Default")
      (node (ref "R30") (pin "1") (pinfunction "1_1") (pintype "passive"))
      (node (ref "U3") (pin "2") (pinfunction "IN_2") (pintype "tri_state"))
    )
    (net (code "48") (name "Net-(U3-OUTH)") (class "Default")
      (node (ref "R34") (pin "2") (pinfunction "2_2") (pintype "passive"))
      (node (ref "U3") (pin "6") (pinfunction "OUTH_6") (pintype "passive"))
    )
    (net (code "49") (name "Net-(U3-OUTL)") (class "Default")
      (node (ref "R35") (pin "2") (pinfunction "2_2") (pintype "passive"))
      (node (ref "U3") (pin "5") (pinfunction "OUTL_5") (pintype "passive"))
    )
    (net (code "50") (name "Net-(U3-VDD)") (class "Default")
      (node (ref "C13") (pin "2") (pinfunction "2_2") (pintype "passive"))
      (node (ref "L9") (pin "2") (pinfunction "2_2") (pintype "passive"))
      (node (ref "U3") (pin "3") (pinfunction "VDD_3") (pintype "power_in"))
    )
    (net (code "51") (name "Net-(U4-EN)") (class "Default")
      (node (ref "R14") (pin "2") (pinfunction "2_2") (pintype "passive"))
      (node (ref "U4") (pin "1") (pinfunction "EN_1") (pintype "input"))
    )
    (net (code "52") (name "Net-(U4-IN)") (class "Default")
      (node (ref "R13") (pin "1") (pinfunction "1_1") (pintype "passive"))
      (node (ref "U4") (pin "2") (pinfunction "IN_2") (pintype "tri_state"))
    )
    (net (code "53") (name "Net-(U4-OUTH)") (class "Default")
      (node (ref "R29") (pin "2") (pinfunction "2_2") (pintype "passive"))
      (node (ref "U4") (pin "6") (pinfunction "OUTH_6") (pintype "passive"))
    )
    (net (code "54") (name "Net-(U4-OUTL)") (class "Default")
      (node (ref "R32") (pin "2") (pinfunction "2_2") (pintype "passive"))
      (node (ref "U4") (pin "5") (pinfunction "OUTL_5") (pintype "passive"))
    )
    (net (code "55") (name "Net-(U4-VDD)") (class "Default")
      (node (ref "C10") (pin "2") (pinfunction "2_2") (pintype "passive"))
      (node (ref "L8") (pin "2") (pinfunction "2_2") (pintype "passive"))
      (node (ref "U4") (pin "3") (pinfunction "VDD_3") (pintype "power_in"))
    )
    (net (code "56") (name "VCC") (class "Default")
      (node (ref "C12") (pin "1") (pinfunction "1_1") (pintype "passive"))
      (node (ref "C14") (pin "1") (pinfunction "1_1") (pintype "passive"))
      (node (ref "C16") (pin "1") (pinfunction "1_1") (pintype "passive"))
      (node (ref "C20") (pin "1") (pinfunction "1_1") (pintype "passive"))
      (node (ref "C9") (pin "1") (pinfunction "1_1") (pintype "passive"))
      (node (ref "DD1") (pin "1") (pinfunction "VBAT_1") (pintype "passive"))
      (node (ref "DD1") (pin "24") (pinfunction "VDD_24") (pintype "passive"))
      (node (ref "DD1") (pin "36") (pinfunction "VDD_36") (pintype "passive"))
      (node (ref "DD1") (pin "48") (pinfunction "VDD_48") (pintype "passive"))
      (node (ref "DD1") (pin "9") (pinfunction "VDDA_9") (pintype "passive"))
      (node (ref "R23") (pin "1") (pinfunction "1_1") (pintype "passive"))
      (node (ref "R26") (pin "1") (pinfunction "1_1") (pintype "passive"))
      (node (ref "U2") (pin "2") (pinfunction "VOUT_2") (pintype "power_in"))
      (node (ref "U2") (pin "4") (pinfunction "VOUT_4") (pintype "power_in"))
    )
    (net (code "57") (name "Vin") (class "Default")
      (node (ref "C1") (pin "1") (pinfunction "1_1") (pintype "passive"))
      (node (ref "L2") (pin "2") (pinfunction "2_2") (pintype "passive"))
      (node (ref "L4") (pin "2") (pinfunction "2_2") (pintype "passive"))
      (node (ref "L5") (pin "2") (pinfunction "2_2") (pintype "passive"))
      (node (ref "P1") (pin "2") (pinfunction "2_2") (pintype "passive"))
      (node (ref "P2") (pin "6") (pinfunction "6_6") (pintype "passive"))
      (node (ref "U2") (pin "3") (pinfunction "VIN_3") (pintype "power_in"))
    )
    (net (code "58") (name "Vlaser1") (class "Default")
      (node (ref "C6") (pin "2") (pinfunction "2_2") (pintype "passive"))
      (node (ref "D1") (pin "2") (pinfunction "K_2") (pintype "passive"))
      (node (ref "L1") (pin "1") (pinfunction "1_1") (pintype "passive"))
      (node (ref "R18") (pin "2") (pinfunction "2_2") (pintype "passive"))
      (node (ref "R5") (pin "2") (pinfunction "2_2") (pintype "passive"))
    )
    (net (code "59") (name "Vlaser2") (class "Default")
      (node (ref "C7") (pin "2") (pinfunction "2_2") (pintype "passive"))
      (node (ref "D2") (pin "2") (pinfunction "K_2") (pintype "passive"))
      (node (ref "L8") (pin "1") (pinfunction "1_1") (pintype "passive"))
      (node (ref "R15") (pin "2") (pinfunction "2_2") (pintype "passive"))
      (node (ref "R8") (pin "2") (pinfunction "2_2") (pintype "passive"))
    )
    (net (code "60") (name "Vlaser3") (class "Default")
      (node (ref "C8") (pin "2") (pinfunction "2_2") (pintype "passive"))
      (node (ref "D3") (pin "2") (pinfunction "K_2") (pintype "passive"))
      (node (ref "L9") (pin "1") (pinfunction "1_1") (pintype "passive"))
      (node (ref "R10") (pin "2") (pinfunction "2_2") (pintype "passive"))
      (node (ref "R24") (pin "2") (pinfunction "2_2") (pintype "passive"))
    )
    (net (code "61") (name "unconnected-(DD1-PA1-Pad11)") (class "Default")
      (node (ref "DD1") (pin "11") (pinfunction "PA1_11") (pintype "passive"))
    )
    (net (code "62") (name "unconnected-(DD1-PA2-Pad12)") (class "Default")
      (node (ref "DD1") (pin "12") (pinfunction "PA2_12") (pintype "passive"))
    )
    (net (code "63") (name "unconnected-(DD1-PA3-Pad13)") (class "Default")
      (node (ref "DD1") (pin "13") (pinfunction "PA3_13") (pintype "passive"))
    )
    (net (code "64") (name "unconnected-(DD1-PA4-Pad14)") (class "Default")
      (node (ref "DD1") (pin "14") (pinfunction "PA4_14") (pintype "passive"))
    )
    (net (code "65") (name "unconnected-(DD1-PA6-Pad16)") (class "Default")
      (node (ref "DD1") (pin "16") (pinfunction "PA6_16") (pintype "passive"))
    )
    (net (code "66") (name "unconnected-(DD1-PA15-Pad38)") (class "Default")
      (node (ref "DD1") (pin "38") (pinfunction "PA15_38") (pintype "passive"))
    )
    (net (code "67") (name "unconnected-(DD1-PB0-Pad18)") (class "Default")
      (node (ref "DD1") (pin "18") (pinfunction "PB0_18") (pintype "passive"))
    )
    (net (code "68") (name "unconnected-(DD1-PB1-Pad19)") (class "Default")
      (node (ref "DD1") (pin "19") (pinfunction "PB1_19") (pintype "passive"))
    )
    (net (code "69") (name "unconnected-(DD1-PB2-Pad20)") (class "Default")
      (node (ref "DD1") (pin "20") (pinfunction "PB2_20") (pintype "passive"))
    )
    (net (code "70") (name "unconnected-(DD1-PB5-Pad41)") (class "Default")
      (node (ref "DD1") (pin "41") (pinfunction "PB5_41") (pintype "passive"))
    )
    (net (code "71") (name "unconnected-(DD1-PB6-Pad42)") (class "Default")
      (node (ref "DD1") (pin "42") (pinfunction "PB6_42") (pintype "passive"))
    )
    (net (code "72") (name "unconnected-(DD1-PB7-Pad43)") (class "Default")
      (node (ref "DD1") (pin "43") (pinfunction "PB7_43") (pintype "passive"))
    )
    (net (code "73") (name "unconnected-(DD1-PB8-Pad45)") (class "Default")
      (node (ref "DD1") (pin "45") (pinfunction "PB8_45") (pintype "passive"))
    )
    (net (code "74") (name "unconnected-(DD1-PB9-Pad46)") (class "Default")
      (node (ref "DD1") (pin "46") (pinfunction "PB9_46") (pintype "passive"))
    )
    (net (code "75") (name "unconnected-(DD1-PB10-Pad21)") (class "Default")
      (node (ref "DD1") (pin "21") (pinfunction "PB10_21") (pintype "passive"))
    )
    (net (code "76") (name "unconnected-(DD1-PB11-Pad22)") (class "Default")
      (node (ref "DD1") (pin "22") (pinfunction "PB11_22") (pintype "passive"))
    )
    (net (code "77") (name "unconnected-(DD1-PB12-Pad25)") (class "Default")
      (node (ref "DD1") (pin "25") (pinfunction "PB12_25") (pintype "passive"))
    )
    (net (code "78") (name "unconnected-(DD1-PB13-Pad26)") (class "Default")
      (node (ref "DD1") (pin "26") (pinfunction "PB13_26") (pintype "passive"))
    )
    (net (code "79") (name "unconnected-(DD1-PB14-Pad27)") (class "Default")
      (node (ref "DD1") (pin "27") (pinfunction "PB14_27") (pintype "passive"))
    )
    (net (code "80") (name "unconnected-(DD1-PB15-Pad28)") (class "Default")
      (node (ref "DD1") (pin "28") (pinfunction "PB15_28") (pintype "passive"))
    )
    (net (code "81") (name "unconnected-(DD1-PC13-Pad2)") (class "Default")
      (node (ref "DD1") (pin "2") (pinfunction "PC13_2") (pintype "passive"))
    )
    (net (code "82") (name "unconnected-(DD1-PC14-Pad3)") (class "Default")
      (node (ref "DD1") (pin "3") (pinfunction "PC14_3") (pintype "passive"))
    )
    (net (code "83") (name "unconnected-(DD1-PC15-Pad4)") (class "Default")
      (node (ref "DD1") (pin "4") (pinfunction "PC15_4") (pintype "passive"))
    )
  )
)
